# 1__schdoc.net
KiCad netlist of a schematic drawn in Altium Designer
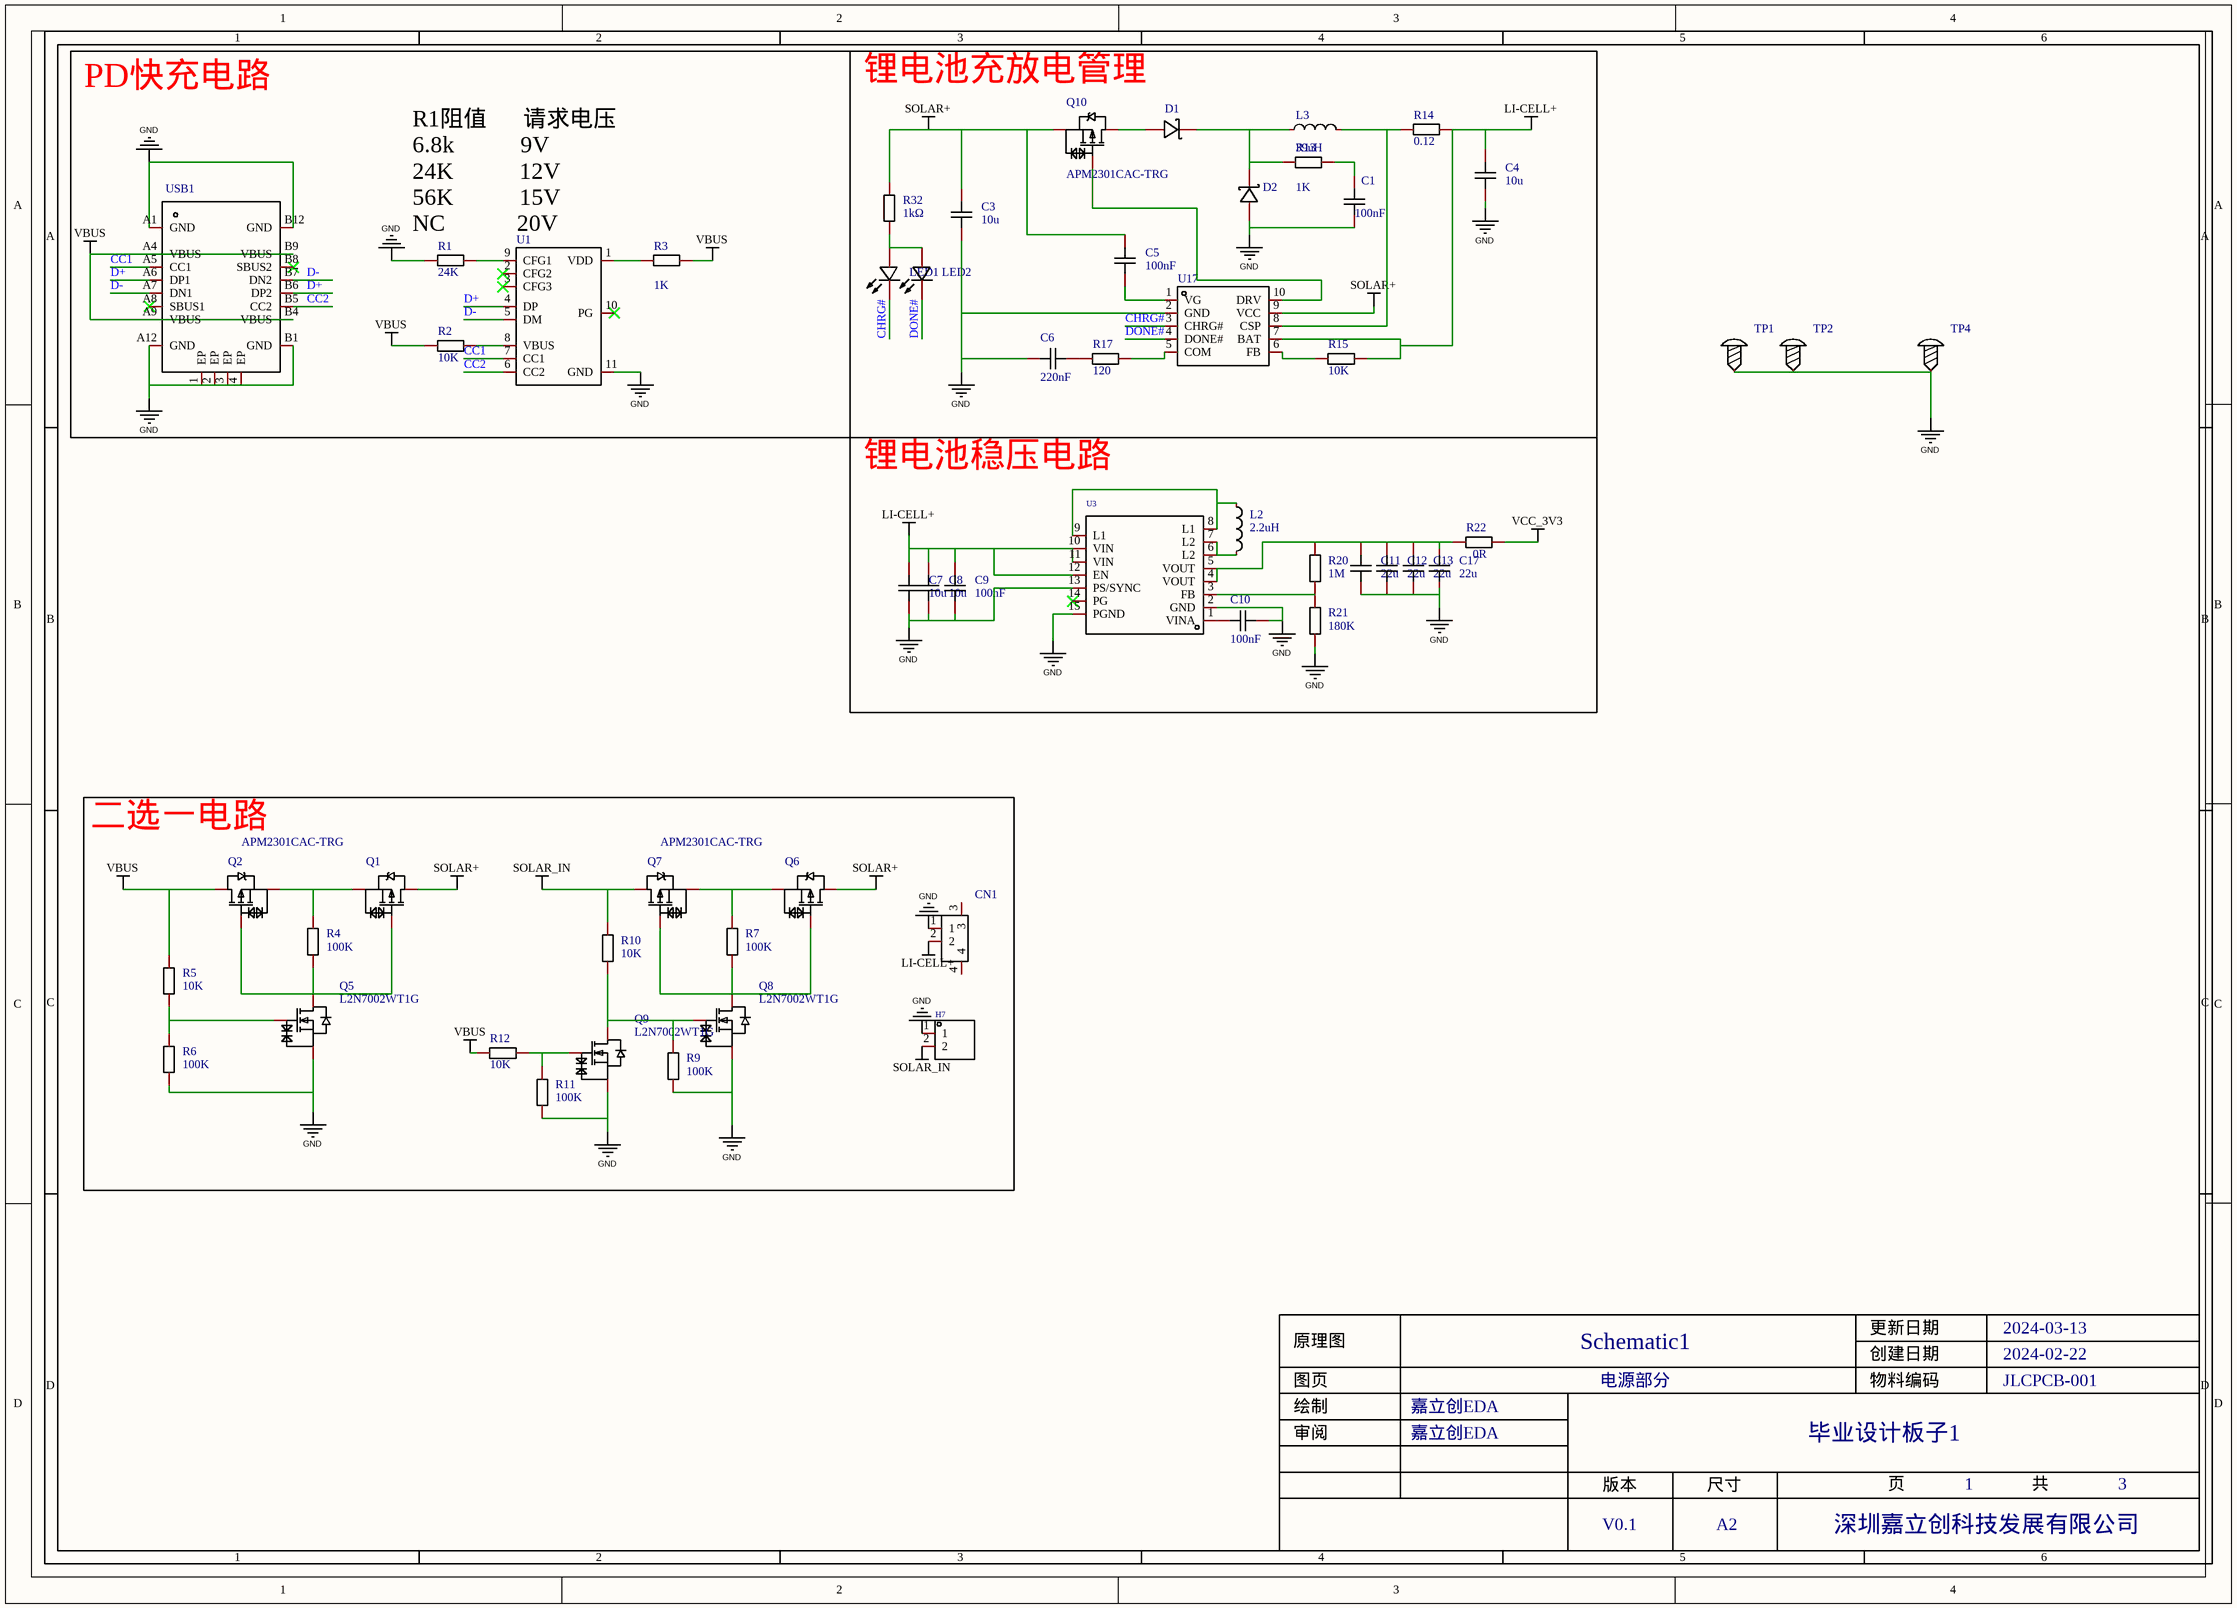
[diagram p0: 1_电源部分.schdoc.schdoc]

(export (version "E")
  (design (tool "Eeschema 10.0.6"))
  (components
    (comp (ref "C1")
      (value "100nF")
      (fields (field (name "Comment") "CAP_0402"))
      (libsource (lib "altium-import") (part "root_1_CAP_0402_"))
    )
    (comp (ref "C3")
      (value "10u")
      (fields (field (name "Comment") "CAP_0805"))
      (libsource (lib "altium-import") (part "root_1_CAP_0805_"))
    )
    (comp (ref "C4")
      (value "10u")
      (fields (field (name "Comment") "CAP_0805"))
      (libsource (lib "altium-import") (part "root_1_CAP_0805_"))
    )
    (comp (ref "C5")
      (value "100nF")
      (fields (field (name "Comment") "CAP_0402"))
      (libsource (lib "altium-import") (part "root_1_CAP_0402_"))
    )
    (comp (ref "C6")
      (value "220nF")
      (fields (field (name "Comment") "CAP_0402"))
      (libsource (lib "altium-import") (part "root_2_CAP_0402_"))
    )
    (comp (ref "C7")
      (value "10u")
      (fields (field (name "Comment") "CAP_0805"))
      (libsource (lib "altium-import") (part "root_1_CAP_0805_"))
    )
    (comp (ref "C8")
      (value "10u")
      (fields (field (name "Comment") "CAP_0805"))
      (libsource (lib "altium-import") (part "root_1_CAP_0805_"))
    )
    (comp (ref "C9")
      (value "100nF")
      (fields (field (name "Comment") "CAP_0402"))
      (libsource (lib "altium-import") (part "root_1_CAP_0402_"))
    )
    (comp (ref "C10")
      (value "100nF")
      (fields (field (name "Comment") "CAP_0402"))
      (libsource (lib "altium-import") (part "root_2_CAP_0402_"))
    )
    (comp (ref "C11")
      (value "22u")
      (fields (field (name "Comment") "CAP_0805"))
      (libsource (lib "altium-import") (part "root_1_CAP_0805_"))
    )
    (comp (ref "C12")
      (value "22u")
      (fields (field (name "Comment") "CAP_0805"))
      (libsource (lib "altium-import") (part "root_1_CAP_0805_"))
    )
    (comp (ref "C13")
      (value "22u")
      (fields (field (name "Comment") "CAP_0805"))
      (libsource (lib "altium-import") (part "root_1_CAP_0805_"))
    )
    (comp (ref "C17")
      (value "22u")
      (fields (field (name "Comment") "CAP_0805"))
      (libsource (lib "altium-import") (part "root_1_CAP_0805_"))
    )
    (comp (ref "CN1")
      (value "HCZZ0021-2")
      (fields (field (name "MANUFACTURER") "HC(虹成电子)"))
      (libsource (lib "altium-import") (part "root_0_HCZZ0021-2_"))
    )
    (comp (ref "D1")
      (value "B340A")
      (description "正向压降(Vf):550mV@3A;直流反向耐压(Vr):40V;平均整流电流(Io):3A;")
      (fields (field (name "MANUFACTURER") "MDD"))
      (libsource (lib "altium-import") (part "root_2_B340A_"))
    )
    (comp (ref "D2")
      (value "B340A")
      (description "正向压降(Vf):550mV@3A;直流反向耐压(Vr):40V;平均整流电流(Io):3A;")
      (fields (field (name "MANUFACTURER") "MDD"))
      (libsource (lib "altium-import") (part "root_3_B340A_"))
    )
    (comp (ref "H7")
      (value "HDR-M_2.54_1x2P")
      (fields (field (name "MANUFACTURER") "Ckmtw(灿科盟)") (field (name "MANUFACTURER PART") "B-2100S02P-A110"))
      (libsource (lib "altium-import") (part "root_0_HDR-M_2.54_1x2P_"))
    )
    (comp (ref "L2")
      (value "2.2uH")
      (fields
        (field (name "MANUFACTURER") "Sunlord(顺络)")
        (field (name "MANUFACTURER PART") "MWSA0402S-2R2MT")
        (field (name "TOLERANCE") "±20%")
      )
      (libsource (lib "altium-import") (part "root_3_MWSA0402S-2R2MT_"))
    )
    (comp (ref "L3")
      (value "39uH")
      (fields
        (field (name "MANUFACTURER") "YJYCOIN(益嘉源)")
        (field (name "MANUFACTURER PART") "YDRH104R-390M")
        (field (name "TOLERANCE") "±20%")
      )
      (libsource (lib "altium-import") (part "root_0_YDRH104R-390M_"))
    )
    (comp (ref "LED1")
      (value "NCD0805R1")
      (fields (field (name "MANUFACTURER") "国星光电"))
      (libsource (lib "altium-import") (part "root_1_NCD0805R1_"))
    )
    (comp (ref "LED2")
      (value "NCD0805R1")
      (fields (field (name "MANUFACTURER") "国星光电"))
      (libsource (lib "altium-import") (part "root_1_NCD0805R1_"))
    )
    (comp (ref "Q1")
      (value "APM2301CAC-TRG")
      (fields (field (name "MANUFACTURER") "Sinopower(大中)"))
      (libsource (lib "altium-import") (part "root_1_mirrored_APM2301CAC-TRG_"))
    )
    (comp (ref "Q2")
      (value "APM2301CAC-TRG")
      (fields
        (field (name "MANUFACTURER") "Sinopower(大中)")
        (field (name "MANUFACTURER PART") "APM2301CAC-TRG")
      )
      (libsource (lib "altium-import") (part "root_1_APM2301CAC-TRG_"))
    )
    (comp (ref "Q5")
      (value "L2N7002WT1G")
      (fields (field (name "MANUFACTURER") "LRC(乐山无线电)") (field (name "MANUFACTURER PART") "L2N7002WT1G"))
      (libsource (lib "altium-import") (part "root_0_L2N7002WT1G_"))
    )
    (comp (ref "Q6")
      (value "APM2301CAC-TRG")
      (fields (field (name "MANUFACTURER") "Sinopower(大中)"))
      (libsource (lib "altium-import") (part "root_1_mirrored_APM2301CAC-TRG_"))
    )
    (comp (ref "Q7")
      (value "APM2301CAC-TRG")
      (fields
        (field (name "MANUFACTURER") "Sinopower(大中)")
        (field (name "MANUFACTURER PART") "APM2301CAC-TRG")
      )
      (libsource (lib "altium-import") (part "root_1_APM2301CAC-TRG_"))
    )
    (comp (ref "Q8")
      (value "L2N7002WT1G")
      (fields (field (name "MANUFACTURER") "LRC(乐山无线电)") (field (name "MANUFACTURER PART") "L2N7002WT1G"))
      (libsource (lib "altium-import") (part "root_0_L2N7002WT1G_"))
    )
    (comp (ref "Q9")
      (value "L2N7002WT1G")
      (fields (field (name "MANUFACTURER") "LRC(乐山无线电)") (field (name "MANUFACTURER PART") "L2N7002WT1G"))
      (libsource (lib "altium-import") (part "root_0_L2N7002WT1G_"))
    )
    (comp (ref "Q10")
      (value "APM2301CAC-TRG")
      (fields
        (field (name "MANUFACTURER") "Sinopower(大中)")
        (field (name "MANUFACTURER PART") "APM2301CAC-TRG")
      )
      (libsource (lib "altium-import") (part "root_1_mirrored_APM2301CAC-TRG_"))
    )
    (comp (ref "R1")
      (value "24K")
      (fields (field (name "Comment") "Res_0402"))
      (libsource (lib "altium-import") (part "root_0_Res_0402_"))
    )
    (comp (ref "R2")
      (value "10K")
      (fields (field (name "Comment") "Res_0402"))
      (libsource (lib "altium-import") (part "root_0_Res_0402_"))
    )
    (comp (ref "R3")
      (value "1K")
      (fields (field (name "Comment") "Res_0402"))
      (libsource (lib "altium-import") (part "root_0_Res_0402_"))
    )
    (comp (ref "R4")
      (value "100K")
      (fields (field (name "Comment") "Res_0402"))
      (libsource (lib "altium-import") (part "root_1_Res_0402_"))
    )
    (comp (ref "R5")
      (value "10K")
      (fields (field (name "Comment") "Res_0402"))
      (libsource (lib "altium-import") (part "root_1_Res_0402_"))
    )
    (comp (ref "R6")
      (value "100K")
      (fields (field (name "Comment") "Res_0402"))
      (libsource (lib "altium-import") (part "root_1_Res_0402_"))
    )
    (comp (ref "R7")
      (value "100K")
      (fields (field (name "Comment") "Res_0402"))
      (libsource (lib "altium-import") (part "root_1_Res_0402_"))
    )
    (comp (ref "R9")
      (value "100K")
      (fields (field (name "Comment") "Res_0402"))
      (libsource (lib "altium-import") (part "root_1_Res_0402_"))
    )
    (comp (ref "R10")
      (value "10K")
      (fields (field (name "Comment") "Res_0402"))
      (libsource (lib "altium-import") (part "root_1_Res_0402_"))
    )
    (comp (ref "R11")
      (value "100K")
      (fields (field (name "Comment") "Res_0402"))
      (libsource (lib "altium-import") (part "root_1_Res_0402_"))
    )
    (comp (ref "R12")
      (value "10K")
      (fields (field (name "Comment") "Res_0402"))
      (libsource (lib "altium-import") (part "root_2_Res_0402_"))
    )
    (comp (ref "R13")
      (value "1K")
      (fields (field (name "Comment") "Res_0402"))
      (libsource (lib "altium-import") (part "root_0_Res_0402_"))
    )
    (comp (ref "R14")
      (value "0.12")
      (fields (field (name "Comment") "Res_1206"))
      (libsource (lib "altium-import") (part "root_0_Res_1206_"))
    )
    (comp (ref "R15")
      (value "10K")
      (fields (field (name "Comment") "Res_0402"))
      (libsource (lib "altium-import") (part "root_0_Res_0402_"))
    )
    (comp (ref "R17")
      (value "120")
      (fields (field (name "Comment") "Res_0402"))
      (libsource (lib "altium-import") (part "root_2_Res_0402_"))
    )
    (comp (ref "R20")
      (value "1M")
      (fields (field (name "Comment") "Res_0402"))
      (libsource (lib "altium-import") (part "root_1_Res_0402_"))
    )
    (comp (ref "R21")
      (value "180K")
      (fields (field (name "Comment") "Res_0402"))
      (libsource (lib "altium-import") (part "root_1_Res_0402_"))
    )
    (comp (ref "R22")
      (value "0R")
      (fields (field (name "Comment") "Res_0402"))
      (libsource (lib "altium-import") (part "root_0_Res_0402_"))
    )
    (comp (ref "R32")
      (value "1kΩ")
      (fields
        (field (name "MANUFACTURER") "UNI-ROYAL(厚声)")
        (field (name "MANUFACTURER PART") "0805W8F4701T5E")
        (field (name "TOLERANCE") "±1%")
      )
      (libsource (lib "altium-import") (part "root_1_0805W8F4701T5E_"))
    )
    (comp (ref "TP1") (value "M3螺丝") (libsource (lib "altium-import") (part "root_0_M3螺丝_")))
    (comp (ref "TP2") (value "M3螺丝") (libsource (lib "altium-import") (part "root_0_M3螺丝_")))
    (comp (ref "TP4") (value "M3螺丝") (libsource (lib "altium-import") (part "root_0_M3螺丝_")))
    (comp (ref "U1")
      (value "CH224K")
      (description "应用功能:USB充电芯片;")
      (fields (field (name "MANUFACTURER") "WCH(南京沁恒)"))
      (libsource (lib "altium-import") (part "root_0_CH224K_"))
    )
    (comp (ref "U3")
      (value "TPS63020DSJT")
      (fields (field (name "MANUFACTURER") "TI(德州仪器)"))
      (libsource (lib "altium-import") (part "root_2_TPS63020DSJT_"))
    )
    (comp (ref "U17")
      (value "CN3781")
      (fields (field (name "MANUFACTURER") "CONSONANCE(上海如韵)"))
      (libsource (lib "altium-import") (part "root_0_CN3781_"))
    )
    (comp (ref "USB1")
      (value "USB_TYPE-C-16P")
      (libsource (lib "altium-import") (part "root_0_USB_TYPE-C-16P_"))
    )
  )
  (nets
    (net (code "1") (name "/CC1") (class "Default")
      (node (ref "U1") (pin "7") (pinfunction "CC1_7") (pintype "passive"))
      (node (ref "USB1") (pin "A5") (pinfunction "CC1_A5") (pintype "passive"))
    )
    (net (code "2") (name "/CC2") (class "Default")
      (node (ref "U1") (pin "6") (pinfunction "CC2_6") (pintype "passive"))
      (node (ref "USB1") (pin "B5") (pinfunction "CC2_B5") (pintype "passive"))
    )
    (net (code "3") (name "/CHRG#") (class "Default")
      (node (ref "LED1") (pin "2") (pinfunction "-_2") (pintype "passive"))
      (node (ref "U17") (pin "3") (pinfunction "CHRG#_3") (pintype "passive"))
    )
    (net (code "4") (name "/D+") (class "Default")
      (node (ref "U1") (pin "4") (pinfunction "DP_4") (pintype "passive"))
      (node (ref "USB1") (pin "A6") (pinfunction "DP1_A6") (pintype "passive"))
      (node (ref "USB1") (pin "B6") (pinfunction "DP2_B6") (pintype "passive"))
    )
    (net (code "5") (name "/D-") (class "Default")
      (node (ref "U1") (pin "5") (pinfunction "DM_5") (pintype "passive"))
      (node (ref "USB1") (pin "A7") (pinfunction "DN1_A7") (pintype "passive"))
      (node (ref "USB1") (pin "B7") (pinfunction "DN2_B7") (pintype "passive"))
    )
    (net (code "6") (name "/DONE#") (class "Default")
      (node (ref "LED2") (pin "2") (pinfunction "-_2") (pintype "passive"))
      (node (ref "U17") (pin "4") (pinfunction "DONE#_4") (pintype "passive"))
    )
    (net (code "7") (name "GND") (class "Default")
      (node (ref "C1") (pin "1") (pinfunction "1_1") (pintype "passive"))
      (node (ref "C10") (pin "1") (pinfunction "1_1") (pintype "passive"))
      (node (ref "C11") (pin "1") (pinfunction "1_1") (pintype "passive"))
      (node (ref "C12") (pin "1") (pinfunction "1_1") (pintype "passive"))
      (node (ref "C13") (pin "1") (pinfunction "1_1") (pintype "passive"))
      (node (ref "C17") (pin "1") (pinfunction "1_1") (pintype "passive"))
      (node (ref "C3") (pin "1") (pinfunction "1_1") (pintype "passive"))
      (node (ref "C4") (pin "1") (pinfunction "1_1") (pintype "passive"))
      (node (ref "C6") (pin "2") (pinfunction "2_2") (pintype "passive"))
      (node (ref "C7") (pin "1") (pinfunction "1_1") (pintype "passive"))
      (node (ref "C8") (pin "1") (pinfunction "1_1") (pintype "passive"))
      (node (ref "C9") (pin "1") (pinfunction "1_1") (pintype "passive"))
      (node (ref "CN1") (pin "1") (pinfunction "1_1") (pintype "passive"))
      (node (ref "D2") (pin "2") (pinfunction "A_2") (pintype "passive"))
      (node (ref "H7") (pin "1") (pinfunction "1_1") (pintype "passive"))
      (node (ref "Q5") (pin "2") (pinfunction "S_2") (pintype "passive"))
      (node (ref "Q8") (pin "2") (pinfunction "S_2") (pintype "passive"))
      (node (ref "Q9") (pin "2") (pinfunction "S_2") (pintype "passive"))
      (node (ref "R1") (pin "1") (pinfunction "1_1") (pintype "passive"))
      (node (ref "R11") (pin "1") (pinfunction "1_1") (pintype "passive"))
      (node (ref "R21") (pin "1") (pinfunction "1_1") (pintype "passive"))
      (node (ref "R6") (pin "1") (pinfunction "1_1") (pintype "passive"))
      (node (ref "R9") (pin "1") (pinfunction "1_1") (pintype "passive"))
      (node (ref "TP1") (pin "1") (pinfunction "1_1") (pintype "passive"))
      (node (ref "TP2") (pin "1") (pinfunction "1_1") (pintype "passive"))
      (node (ref "TP4") (pin "1") (pinfunction "1_1") (pintype "passive"))
      (node (ref "U1") (pin "11") (pinfunction "GND_11") (pintype "passive"))
      (node (ref "U17") (pin "2") (pinfunction "GND_2") (pintype "passive"))
      (node (ref "U3") (pin "13") (pinfunction "PS/SYNC_13") (pintype "passive"))
      (node (ref "U3") (pin "15") (pinfunction "PGND_15") (pintype "passive"))
      (node (ref "U3") (pin "2") (pinfunction "GND_2") (pintype "passive"))
      (node (ref "USB1") (pin "1") (pinfunction "EP_1") (pintype "passive"))
      (node (ref "USB1") (pin "2") (pinfunction "EP_2") (pintype "passive"))
      (node (ref "USB1") (pin "3") (pinfunction "EP_3") (pintype "passive"))
      (node (ref "USB1") (pin "4") (pinfunction "EP_4") (pintype "passive"))
      (node (ref "USB1") (pin "A1") (pinfunction "GND_A1") (pintype "passive"))
      (node (ref "USB1") (pin "A12") (pinfunction "GND_A12") (pintype "passive"))
      (node (ref "USB1") (pin "B1") (pinfunction "GND_B1") (pintype "passive"))
      (node (ref "USB1") (pin "B12") (pinfunction "GND_B12") (pintype "passive"))
    )
    (net (code "8") (name "LI-CELL+") (class "Default")
      (node (ref "C4") (pin "2") (pinfunction "2_2") (pintype "passive"))
      (node (ref "C7") (pin "2") (pinfunction "2_2") (pintype "passive"))
      (node (ref "C8") (pin "2") (pinfunction "2_2") (pintype "passive"))
      (node (ref "C9") (pin "2") (pinfunction "2_2") (pintype "passive"))
      (node (ref "CN1") (pin "2") (pinfunction "2_2") (pintype "passive"))
      (node (ref "R14") (pin "2") (pinfunction "2_2") (pintype "passive"))
      (node (ref "R15") (pin "2") (pinfunction "2_2") (pintype "passive"))
      (node (ref "U17") (pin "7") (pinfunction "BAT_7") (pintype "passive"))
      (node (ref "U3") (pin "10") (pinfunction "VIN_10") (pintype "passive"))
      (node (ref "U3") (pin "11") (pinfunction "VIN_11") (pintype "passive"))
      (node (ref "U3") (pin "12") (pinfunction "EN_12") (pintype "passive"))
    )
    (net (code "9") (name "Net-(C1-Pad2)") (class "Default")
      (node (ref "C1") (pin "2") (pinfunction "2_2") (pintype "passive"))
      (node (ref "R13") (pin "2") (pinfunction "2_2") (pintype "passive"))
    )
    (net (code "10") (name "Net-(C6-Pad1)") (class "Default")
      (node (ref "C6") (pin "1") (pinfunction "1_1") (pintype "passive"))
      (node (ref "R17") (pin "2") (pinfunction "2_2") (pintype "passive"))
    )
    (net (code "11") (name "Net-(C11-Pad2)") (class "Default")
      (node (ref "C11") (pin "2") (pinfunction "2_2") (pintype "passive"))
      (node (ref "C12") (pin "2") (pinfunction "2_2") (pintype "passive"))
      (node (ref "C13") (pin "2") (pinfunction "2_2") (pintype "passive"))
      (node (ref "C17") (pin "2") (pinfunction "2_2") (pintype "passive"))
      (node (ref "R20") (pin "2") (pinfunction "2_2") (pintype "passive"))
      (node (ref "R22") (pin "1") (pinfunction "1_1") (pintype "passive"))
      (node (ref "U3") (pin "4") (pinfunction "VOUT_4") (pintype "passive"))
      (node (ref "U3") (pin "5") (pinfunction "VOUT_5") (pintype "passive"))
    )
    (net (code "12") (name "Net-(D1-A)") (class "Default")
      (node (ref "D1") (pin "2") (pinfunction "A_2") (pintype "passive"))
      (node (ref "Q10") (pin "3") (pinfunction "D_3") (pintype "passive"))
    )
    (net (code "13") (name "Net-(D1-K)") (class "Default")
      (node (ref "D1") (pin "1") (pinfunction "K_1") (pintype "passive"))
      (node (ref "D2") (pin "1") (pinfunction "K_1") (pintype "passive"))
      (node (ref "L3") (pin "1") (pinfunction "1_1") (pintype "passive"))
      (node (ref "R13") (pin "1") (pinfunction "1_1") (pintype "passive"))
    )
    (net (code "14") (name "Net-(L2-Pad1)") (class "Default")
      (node (ref "L2") (pin "1") (pinfunction "1_1") (pintype "passive"))
      (node (ref "U3") (pin "8") (pinfunction "L1_8") (pintype "passive"))
      (node (ref "U3") (pin "9") (pinfunction "L1_9") (pintype "passive"))
    )
    (net (code "15") (name "Net-(L2-Pad2)") (class "Default")
      (node (ref "L2") (pin "2") (pinfunction "2_2") (pintype "passive"))
      (node (ref "U3") (pin "6") (pinfunction "L2_6") (pintype "passive"))
      (node (ref "U3") (pin "7") (pinfunction "L2_7") (pintype "passive"))
    )
    (net (code "16") (name "Net-(LED1-+)") (class "Default")
      (node (ref "LED1") (pin "1") (pinfunction "+_1") (pintype "passive"))
      (node (ref "LED2") (pin "1") (pinfunction "+_1") (pintype "passive"))
      (node (ref "R32") (pin "1") (pinfunction "1_1") (pintype "passive"))
    )
    (net (code "17") (name "Net-(Q1-G)") (class "Default")
      (node (ref "Q1") (pin "1") (pinfunction "G_1") (pintype "passive"))
      (node (ref "Q2") (pin "1") (pinfunction "G_1") (pintype "passive"))
      (node (ref "Q5") (pin "3") (pinfunction "D_3") (pintype "passive"))
      (node (ref "R4") (pin "1") (pinfunction "1_1") (pintype "passive"))
    )
    (net (code "18") (name "Net-(Q1-S)") (class "Default")
      (node (ref "Q1") (pin "2") (pinfunction "S_2") (pintype "passive"))
      (node (ref "Q2") (pin "2") (pinfunction "S_2") (pintype "passive"))
      (node (ref "R4") (pin "2") (pinfunction "2_2") (pintype "passive"))
    )
    (net (code "19") (name "Net-(Q5-G)") (class "Default")
      (node (ref "Q5") (pin "1") (pinfunction "G_1") (pintype "passive"))
      (node (ref "R5") (pin "1") (pinfunction "1_1") (pintype "passive"))
      (node (ref "R6") (pin "2") (pinfunction "2_2") (pintype "passive"))
    )
    (net (code "20") (name "Net-(Q6-G)") (class "Default")
      (node (ref "Q6") (pin "1") (pinfunction "G_1") (pintype "passive"))
      (node (ref "Q7") (pin "1") (pinfunction "G_1") (pintype "passive"))
      (node (ref "Q8") (pin "3") (pinfunction "D_3") (pintype "passive"))
      (node (ref "R7") (pin "1") (pinfunction "1_1") (pintype "passive"))
    )
    (net (code "21") (name "Net-(Q6-S)") (class "Default")
      (node (ref "Q6") (pin "2") (pinfunction "S_2") (pintype "passive"))
      (node (ref "Q7") (pin "2") (pinfunction "S_2") (pintype "passive"))
      (node (ref "R7") (pin "2") (pinfunction "2_2") (pintype "passive"))
    )
    (net (code "22") (name "Net-(Q8-G)") (class "Default")
      (node (ref "Q8") (pin "1") (pinfunction "G_1") (pintype "passive"))
      (node (ref "Q9") (pin "3") (pinfunction "D_3") (pintype "passive"))
      (node (ref "R10") (pin "1") (pinfunction "1_1") (pintype "passive"))
      (node (ref "R9") (pin "2") (pinfunction "2_2") (pintype "passive"))
    )
    (net (code "23") (name "Net-(Q9-G)") (class "Default")
      (node (ref "Q9") (pin "1") (pinfunction "G_1") (pintype "passive"))
      (node (ref "R11") (pin "2") (pinfunction "2_2") (pintype "passive"))
      (node (ref "R12") (pin "1") (pinfunction "1_1") (pintype "passive"))
    )
    (net (code "24") (name "Net-(Q10-G)") (class "Default")
      (node (ref "Q10") (pin "1") (pinfunction "G_1") (pintype "passive"))
      (node (ref "U17") (pin "10") (pinfunction "DRV_10") (pintype "passive"))
    )
    (net (code "25") (name "Net-(U1-CFG1)") (class "Default")
      (node (ref "R1") (pin "2") (pinfunction "2_2") (pintype "passive"))
      (node (ref "U1") (pin "9") (pinfunction "CFG1_9") (pintype "passive"))
    )
    (net (code "26") (name "Net-(U1-VBUS)") (class "Default")
      (node (ref "R2") (pin "2") (pinfunction "2_2") (pintype "passive"))
      (node (ref "U1") (pin "8") (pinfunction "VBUS_8") (pintype "passive"))
    )
    (net (code "27") (name "Net-(U1-VDD)") (class "Default")
      (node (ref "R3") (pin "1") (pinfunction "1_1") (pintype "passive"))
      (node (ref "U1") (pin "1") (pinfunction "VDD_1") (pintype "passive"))
    )
    (net (code "28") (name "Net-(U3-FB)") (class "Default")
      (node (ref "R20") (pin "1") (pinfunction "1_1") (pintype "passive"))
      (node (ref "R21") (pin "2") (pinfunction "2_2") (pintype "passive"))
      (node (ref "U3") (pin "3") (pinfunction "FB_3") (pintype "passive"))
    )
    (net (code "29") (name "Net-(U3-VINA)") (class "Default")
      (node (ref "C10") (pin "2") (pinfunction "2_2") (pintype "passive"))
      (node (ref "U3") (pin "1") (pinfunction "VINA_1") (pintype "passive"))
    )
    (net (code "30") (name "Net-(U17-COM)") (class "Default")
      (node (ref "R17") (pin "1") (pinfunction "1_1") (pintype "passive"))
      (node (ref "U17") (pin "5") (pinfunction "COM_5") (pintype "passive"))
    )
    (net (code "31") (name "Net-(U17-CSP)") (class "Default")
      (node (ref "L3") (pin "2") (pinfunction "2_2") (pintype "passive"))
      (node (ref "R14") (pin "1") (pinfunction "1_1") (pintype "passive"))
      (node (ref "U17") (pin "8") (pinfunction "CSP_8") (pintype "passive"))
    )
    (net (code "32") (name "Net-(U17-FB)") (class "Default")
      (node (ref "R15") (pin "1") (pinfunction "1_1") (pintype "passive"))
      (node (ref "U17") (pin "6") (pinfunction "FB_6") (pintype "passive"))
    )
    (net (code "33") (name "Net-(U17-VG)") (class "Default")
      (node (ref "C5") (pin "1") (pinfunction "1_1") (pintype "passive"))
      (node (ref "U17") (pin "1") (pinfunction "VG_1") (pintype "passive"))
    )
    (net (code "34") (name "SOLAR+") (class "Default")
      (node (ref "C3") (pin "2") (pinfunction "2_2") (pintype "passive"))
      (node (ref "C5") (pin "2") (pinfunction "2_2") (pintype "passive"))
      (node (ref "Q1") (pin "3") (pinfunction "D_3") (pintype "passive"))
      (node (ref "Q10") (pin "2") (pinfunction "S_2") (pintype "passive"))
      (node (ref "Q6") (pin "3") (pinfunction "D_3") (pintype "passive"))
      (node (ref "R32") (pin "2") (pinfunction "2_2") (pintype "passive"))
      (node (ref "U17") (pin "9") (pinfunction "VCC_9") (pintype "passive"))
    )
    (net (code "35") (name "SOLAR_IN") (class "Default")
      (node (ref "H7") (pin "2") (pinfunction "2_2") (pintype "passive"))
      (node (ref "Q7") (pin "3") (pinfunction "D_3") (pintype "passive"))
      (node (ref "R10") (pin "2") (pinfunction "2_2") (pintype "passive"))
    )
    (net (code "36") (name "VBUS") (class "Default")
      (node (ref "Q2") (pin "3") (pinfunction "D_3") (pintype "passive"))
      (node (ref "R12") (pin "2") (pinfunction "2_2") (pintype "passive"))
      (node (ref "R2") (pin "1") (pinfunction "1_1") (pintype "passive"))
      (node (ref "R3") (pin "2") (pinfunction "2_2") (pintype "passive"))
      (node (ref "R5") (pin "2") (pinfunction "2_2") (pintype "passive"))
      (node (ref "USB1") (pin "A4") (pinfunction "VBUS_A4") (pintype "passive"))
      (node (ref "USB1") (pin "A9") (pinfunction "VBUS_A9") (pintype "passive"))
      (node (ref "USB1") (pin "B4") (pinfunction "VBUS_B4") (pintype "passive"))
      (node (ref "USB1") (pin "B9") (pinfunction "VBUS_B9") (pintype "passive"))
    )
    (net (code "37") (name "VCC_3V3") (class "Default")
      (node (ref "R22") (pin "2") (pinfunction "2_2") (pintype "passive"))
    )
    (net (code "38") (name "unconnected-(CN1-Pad3)") (class "Default")
      (node (ref "CN1") (pin "3") (pinfunction "3_3") (pintype "passive"))
    )
    (net (code "39") (name "unconnected-(CN1-Pad4)") (class "Default")
      (node (ref "CN1") (pin "4") (pinfunction "4_4") (pintype "passive"))
    )
    (net (code "40") (name "unconnected-(U1-CFG2-Pad2)") (class "Default")
      (node (ref "U1") (pin "2") (pinfunction "CFG2_2") (pintype "passive+no_connect"))
    )
    (net (code "41") (name "unconnected-(U1-CFG3-Pad3)") (class "Default")
      (node (ref "U1") (pin "3") (pinfunction "CFG3_3") (pintype "passive+no_connect"))
    )
    (net (code "42") (name "unconnected-(U1-PG-Pad10)") (class "Default")
      (node (ref "U1") (pin "10") (pinfunction "PG_10") (pintype "passive+no_connect"))
    )
    (net (code "43") (name "unconnected-(U3-PG-Pad14)") (class "Default")
      (node (ref "U3") (pin "14") (pinfunction "PG_14") (pintype "passive+no_connect"))
    )
    (net (code "44") (name "unconnected-(USB1-SBUS1-PadA8)") (class "Default")
      (node (ref "USB1") (pin "A8") (pinfunction "SBUS1_A8") (pintype "passive+no_connect"))
    )
    (net (code "45") (name "unconnected-(USB1-SBUS2-PadB8)") (class "Default")
      (node (ref "USB1") (pin "B8") (pinfunction "SBUS2_B8") (pintype "passive+no_connect"))
    )
  )
)
